# DTX1-1740P.net
KiCad netlist of a schematic drawn in Altium Designer
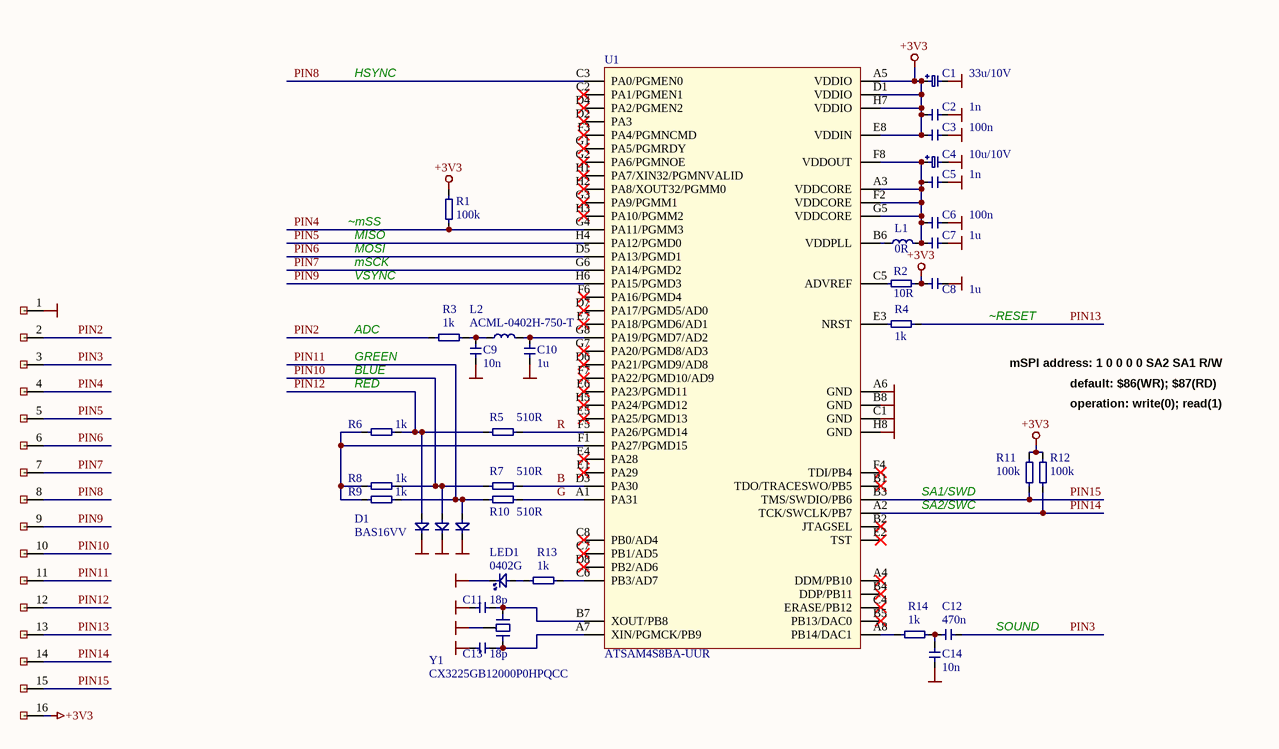
[diagram p0: DTX1-1740P.SchDoc]

(export (version "E")
  (design (tool "Eeschema 10.0.6"))
  (components
    (comp (ref "C1")
      (value "33u/10V")
      (footprint "Case A (3216)")
      (description "Polar capacitor")
      (libsource (lib "Discretes") (part "Capacitor+"))
    )
    (comp (ref "C2")
      (value "1n")
      (footprint "_0201")
      (description "Capacitor")
      (libsource (lib "Discretes") (part "Capacitor"))
    )
    (comp (ref "C3")
      (value "100n")
      (footprint "_0201")
      (description "Capacitor")
      (libsource (lib "Discretes") (part "Capacitor"))
    )
    (comp (ref "C4")
      (value "10u/10V")
      (footprint "_0805+")
      (description "Polar capacitor")
      (libsource (lib "Discretes") (part "Capacitor+"))
    )
    (comp (ref "C5")
      (value "1n")
      (footprint "_0201")
      (description "Capacitor")
      (libsource (lib "Discretes") (part "Capacitor"))
    )
    (comp (ref "C6")
      (value "100n")
      (footprint "_0201")
      (description "Capacitor")
      (libsource (lib "Discretes") (part "Capacitor"))
    )
    (comp (ref "C7")
      (value "1u")
      (footprint "_0201")
      (description "Capacitor")
      (libsource (lib "Discretes") (part "Capacitor"))
    )
    (comp (ref "C8")
      (value "1u")
      (footprint "_0201")
      (description "Capacitor")
      (libsource (lib "Discretes") (part "Capacitor"))
    )
    (comp (ref "C9")
      (value "10n")
      (footprint "_0201")
      (description "Capacitor")
      (libsource (lib "Discretes") (part "Capacitor"))
    )
    (comp (ref "C10")
      (value "1u")
      (footprint "_0201")
      (description "Capacitor")
      (libsource (lib "Discretes") (part "Capacitor"))
    )
    (comp (ref "C11")
      (value "18p")
      (footprint "_0201")
      (description "Capacitor")
      (libsource (lib "Discretes") (part "Capacitor"))
    )
    (comp (ref "C12")
      (value "470n")
      (footprint "_0201")
      (description "Capacitor")
      (libsource (lib "Discretes") (part "Capacitor"))
    )
    (comp (ref "C13")
      (value "18p")
      (footprint "_0201")
      (description "Capacitor")
      (libsource (lib "Discretes") (part "Capacitor"))
    )
    (comp (ref "C14")
      (value "10n")
      (footprint "_0201")
      (description "Capacitor")
      (libsource (lib "Discretes") (part "Capacitor"))
    )
    (comp (ref "D1")
      (value "BAS16VV")
      (footprint "SOT666-6")
      (description "Diode (triple)")
      (libsource (lib "Discretes") (part "Diode Triple"))
    )
    (comp (ref "L1")
      (value "0R")
      (footprint "_0402")
      (description "Inductor")
      (libsource (lib "Discretes") (part "Inductor"))
    )
    (comp (ref "L2")
      (value "ACML-0402H-750-T")
      (footprint "_0402")
      (description "Inductor")
      (libsource (lib "Discretes") (part "Inductor"))
    )
    (comp (ref "LED1")
      (value "0402G")
      (footprint "_0402+")
      (description "Light Emitting Diode")
      (libsource (lib "Discretes") (part "LED"))
    )
    (comp (ref "PIN1")
      (value "Pin/Pad")
      (footprint "Pad T/H 45/90")
      (description "Single pin/pad")
      (libsource (lib "") (part "Pin/Pad_5"))
    )
    (comp (ref "PIN2")
      (value "Pin/Pad")
      (footprint "Pad T/H 45/90")
      (description "Single pin/pad")
      (libsource (lib "") (part "Pin/Pad_1"))
    )
    (comp (ref "PIN3")
      (value "Pin/Pad")
      (footprint "Pad T/H 45/90")
      (description "Single pin/pad")
      (libsource (lib "") (part "Pin/Pad_2"))
    )
    (comp (ref "PIN4")
      (value "Pin/Pad")
      (footprint "Pad T/H 45/90")
      (description "Single pin/pad")
      (libsource (lib "Connectors") (part "Pin/Pad"))
    )
    (comp (ref "PIN5")
      (value "Pin/Pad")
      (footprint "Pad T/H 45/90")
      (description "Single pin/pad")
      (libsource (lib "") (part "Pin/Pad_14"))
    )
    (comp (ref "PIN6")
      (value "Pin/Pad")
      (footprint "Pad T/H 45/90")
      (description "Single pin/pad")
      (libsource (lib "") (part "Pin/Pad_7"))
    )
    (comp (ref "PIN7")
      (value "Pin/Pad")
      (footprint "Pad T/H 45/90")
      (description "Single pin/pad")
      (libsource (lib "") (part "Pin/Pad_6"))
    )
    (comp (ref "PIN8")
      (value "Pin/Pad")
      (footprint "Pad T/H 45/90")
      (description "Single pin/pad")
      (libsource (lib "") (part "Pin/Pad_11"))
    )
    (comp (ref "PIN9")
      (value "Pin/Pad")
      (footprint "Pad T/H 45/90")
      (description "Single pin/pad")
      (libsource (lib "") (part "Pin/Pad_9"))
    )
    (comp (ref "PIN10")
      (value "Pin/Pad")
      (footprint "Pad T/H 45/90")
      (description "Single pin/pad")
      (libsource (lib "") (part "Pin/Pad_15"))
    )
    (comp (ref "PIN11")
      (value "Pin/Pad")
      (footprint "Pad T/H 45/90")
      (description "Single pin/pad")
      (libsource (lib "") (part "Pin/Pad_12"))
    )
    (comp (ref "PIN12")
      (value "Pin/Pad")
      (footprint "Pad T/H 45/90")
      (description "Single pin/pad")
      (libsource (lib "") (part "Pin/Pad_10"))
    )
    (comp (ref "PIN13")
      (value "Pin/Pad")
      (footprint "Pad T/H 45/90")
      (description "Single pin/pad")
      (libsource (lib "") (part "Pin/Pad_4"))
    )
    (comp (ref "PIN14")
      (value "Pin/Pad")
      (footprint "Pad T/H 45/90")
      (description "Single pin/pad")
      (libsource (lib "") (part "Pin/Pad_8"))
    )
    (comp (ref "PIN15")
      (value "Pin/Pad")
      (footprint "Pad T/H 45/90")
      (description "Single pin/pad")
      (libsource (lib "") (part "Pin/Pad_13"))
    )
    (comp (ref "PIN16")
      (value "Pin/Pad")
      (footprint "Pad T/H 45/90")
      (description "Single pin/pad")
      (libsource (lib "") (part "Pin/Pad_3"))
    )
    (comp (ref "R1")
      (value "100k")
      (footprint "_0201")
      (description "Resistor")
      (libsource (lib "") (part "Resistor_1"))
    )
    (comp (ref "R2")
      (value "10R")
      (footprint "_0201")
      (description "Resistor")
      (libsource (lib "Discretes") (part "Resistor"))
    )
    (comp (ref "R3")
      (value "1k")
      (footprint "_0201")
      (description "Resistor")
      (libsource (lib "Discretes") (part "Resistor"))
    )
    (comp (ref "R4")
      (value "1k")
      (footprint "_0201")
      (description "Resistor")
      (libsource (lib "Discretes") (part "Resistor"))
    )
    (comp (ref "R5")
      (value "510R")
      (footprint "_0201")
      (description "Resistor")
      (libsource (lib "Discretes") (part "Resistor"))
    )
    (comp (ref "R6")
      (value "1k")
      (footprint "_0201")
      (description "Resistor")
      (libsource (lib "Discretes") (part "Resistor"))
    )
    (comp (ref "R7")
      (value "510R")
      (footprint "_0201")
      (description "Resistor")
      (libsource (lib "Discretes") (part "Resistor"))
    )
    (comp (ref "R8")
      (value "1k")
      (footprint "_0201")
      (description "Resistor")
      (libsource (lib "Discretes") (part "Resistor"))
    )
    (comp (ref "R9")
      (value "1k")
      (footprint "_0201")
      (description "Resistor")
      (libsource (lib "Discretes") (part "Resistor"))
    )
    (comp (ref "R10")
      (value "510R")
      (footprint "_0201")
      (description "Resistor")
      (libsource (lib "Discretes") (part "Resistor"))
    )
    (comp (ref "R11")
      (value "100k")
      (footprint "_0201")
      (description "Resistor")
      (libsource (lib "") (part "Resistor_1"))
    )
    (comp (ref "R12")
      (value "100k")
      (footprint "_0201")
      (description "Resistor")
      (libsource (lib "") (part "Resistor_1"))
    )
    (comp (ref "R13")
      (value "1k")
      (footprint "_0201")
      (description "Resistor")
      (libsource (lib "Discretes") (part "Resistor"))
    )
    (comp (ref "R14")
      (value "1k")
      (footprint "_0201")
      (description "Resistor")
      (libsource (lib "") (part "Resistor_2"))
    )
    (comp (ref "U1")
      (value "ATSAM4S8BA-UUR")
      (footprint "WLCSP64")
      (description "ARM Cortex M4-based Flash MCU")
      (fields (field (name "MANUFACTURER") "Atmel"))
      (libsource (lib "IC Microcontrollers and Processors") (part "AT91SAM4S16Bx WLCSP64"))
    )
    (comp (ref "Y1")
      (value "CX3225GB12000P0HPQCC")
      (footprint "Crystal 32x25 (4)")
      (description "Crystal Resonator")
      (libsource (lib "Discretes") (part "Crystal (ground)"))
    )
  )
  (nets
    (net (code "1") (name "+3V3") (class "Default")
      (node (ref "C1") (pin "1") (pintype "passive"))
      (node (ref "C2") (pin "1") (pintype "passive"))
      (node (ref "C3") (pin "1") (pintype "passive"))
      (node (ref "C8") (pin "1") (pintype "passive"))
      (node (ref "PIN16") (pin "16") (pintype "passive"))
      (node (ref "R1") (pin "2") (pintype "passive"))
      (node (ref "R11") (pin "2") (pintype "passive"))
      (node (ref "R12") (pin "2") (pintype "passive"))
      (node (ref "R2") (pin "2") (pintype "passive"))
      (node (ref "U1") (pin "A5") (pinfunction "VDDIO_A5") (pintype "passive"))
      (node (ref "U1") (pin "D1") (pinfunction "VDDIO_D1") (pintype "passive"))
      (node (ref "U1") (pin "E8") (pinfunction "VDDIN_E8") (pintype "passive"))
      (node (ref "U1") (pin "H7") (pinfunction "VDDIO_H7") (pintype "passive"))
    )
    (net (code "2") (name "/B") (class "Default")
      (node (ref "R7") (pin "2") (pintype "passive"))
      (node (ref "U1") (pin "D3") (pinfunction "PA30_D3") (pintype "passive"))
    )
    (net (code "3") (name "/G") (class "Default")
      (node (ref "R10") (pin "2") (pintype "passive"))
      (node (ref "U1") (pin "A1") (pinfunction "PA31_A1") (pintype "passive"))
    )
    (net (code "4") (name "/PIN2") (class "Default")
      (node (ref "PIN2") (pin "2") (pintype "passive"))
      (node (ref "R3") (pin "1") (pintype "passive"))
    )
    (net (code "5") (name "/PIN3") (class "Default")
      (node (ref "C12") (pin "2") (pintype "passive"))
      (node (ref "PIN3") (pin "3") (pintype "passive"))
    )
    (net (code "6") (name "/PIN4") (class "Default")
      (node (ref "PIN4") (pin "4") (pintype "passive"))
      (node (ref "R1") (pin "1") (pintype "passive"))
      (node (ref "U1") (pin "G4") (pinfunction "PA11/PGMM3_G4") (pintype "passive"))
    )
    (net (code "7") (name "/PIN5") (class "Default")
      (node (ref "PIN5") (pin "5") (pintype "passive"))
      (node (ref "U1") (pin "H4") (pinfunction "PA12/PGMD0_H4") (pintype "passive"))
    )
    (net (code "8") (name "/PIN6") (class "Default")
      (node (ref "PIN6") (pin "6") (pintype "passive"))
      (node (ref "U1") (pin "D5") (pinfunction "PA13/PGMD1_D5") (pintype "passive"))
    )
    (net (code "9") (name "/PIN7") (class "Default")
      (node (ref "PIN7") (pin "7") (pintype "passive"))
      (node (ref "U1") (pin "G6") (pinfunction "PA14/PGMD2_G6") (pintype "passive"))
    )
    (net (code "10") (name "/PIN8") (class "Default")
      (node (ref "PIN8") (pin "8") (pintype "passive"))
      (node (ref "U1") (pin "C3") (pinfunction "PA0/PGMEN0_C3") (pintype "passive"))
    )
    (net (code "11") (name "/PIN9") (class "Default")
      (node (ref "PIN9") (pin "9") (pintype "passive"))
      (node (ref "U1") (pin "H6") (pinfunction "PA15/PGMD3_H6") (pintype "passive"))
    )
    (net (code "12") (name "/PIN10") (class "Default")
      (node (ref "D1") (pin "2") (pintype "passive"))
      (node (ref "PIN10") (pin "10") (pintype "passive"))
      (node (ref "R7") (pin "1") (pintype "passive"))
      (node (ref "R8") (pin "2") (pintype "passive"))
    )
    (net (code "13") (name "/PIN11") (class "Default")
      (node (ref "D1") (pin "3") (pintype "passive"))
      (node (ref "PIN11") (pin "11") (pintype "passive"))
      (node (ref "R10") (pin "1") (pintype "passive"))
      (node (ref "R9") (pin "2") (pintype "passive"))
    )
    (net (code "14") (name "/PIN12") (class "Default")
      (node (ref "D1") (pin "1") (pintype "passive"))
      (node (ref "PIN12") (pin "12") (pintype "passive"))
      (node (ref "R5") (pin "1") (pintype "passive"))
      (node (ref "R6") (pin "2") (pintype "passive"))
    )
    (net (code "15") (name "/PIN13") (class "Default")
      (node (ref "PIN13") (pin "13") (pintype "passive"))
      (node (ref "R4") (pin "2") (pintype "passive"))
    )
    (net (code "16") (name "/PIN14") (class "Default")
      (node (ref "PIN14") (pin "14") (pintype "passive"))
      (node (ref "R12") (pin "1") (pintype "passive"))
      (node (ref "U1") (pin "A2") (pinfunction "TCK/SWCLK/PB7_A2") (pintype "passive"))
    )
    (net (code "17") (name "/PIN15") (class "Default")
      (node (ref "PIN15") (pin "15") (pintype "passive"))
      (node (ref "R11") (pin "1") (pintype "passive"))
      (node (ref "U1") (pin "B3") (pinfunction "TMS/SWDIO/PB6_B3") (pintype "passive"))
    )
    (net (code "18") (name "/R") (class "Default")
      (node (ref "R5") (pin "2") (pintype "passive"))
      (node (ref "U1") (pin "F5") (pinfunction "PA26/PGMD14_F5") (pintype "passive"))
    )
    (net (code "19") (name "GND") (class "Default")
      (node (ref "C1") (pin "2") (pintype "passive"))
      (node (ref "C10") (pin "1") (pintype "passive"))
      (node (ref "C11") (pin "1") (pintype "passive"))
      (node (ref "C13") (pin "1") (pintype "passive"))
      (node (ref "C14") (pin "1") (pintype "passive"))
      (node (ref "C2") (pin "2") (pintype "passive"))
      (node (ref "C3") (pin "2") (pintype "passive"))
      (node (ref "C4") (pin "2") (pintype "passive"))
      (node (ref "C5") (pin "2") (pintype "passive"))
      (node (ref "C6") (pin "2") (pintype "passive"))
      (node (ref "C7") (pin "2") (pintype "passive"))
      (node (ref "C8") (pin "2") (pintype "passive"))
      (node (ref "C9") (pin "1") (pintype "passive"))
      (node (ref "D1") (pin "4") (pintype "passive"))
      (node (ref "D1") (pin "5") (pintype "passive"))
      (node (ref "D1") (pin "6") (pintype "passive"))
      (node (ref "LED1") (pin "1") (pintype "passive"))
      (node (ref "PIN1") (pin "1") (pintype "passive"))
      (node (ref "U1") (pin "A6") (pinfunction "GND_A6") (pintype "passive"))
      (node (ref "U1") (pin "B8") (pinfunction "GND_B8") (pintype "passive"))
      (node (ref "U1") (pin "C1") (pinfunction "GND_C1") (pintype "passive"))
      (node (ref "U1") (pin "H8") (pinfunction "GND_H8") (pintype "passive"))
      (node (ref "Y1") (pin "3") (pinfunction "GND_3") (pintype "passive"))
    )
    (net (code "20") (name "Net-(C9-Pad2)") (class "Default")
      (node (ref "C9") (pin "2") (pintype "passive"))
      (node (ref "L2") (pin "1") (pintype "passive"))
      (node (ref "R3") (pin "2") (pintype "passive"))
    )
    (net (code "21") (name "Net-(C12-Pad1)") (class "Default")
      (node (ref "C12") (pin "1") (pintype "passive"))
      (node (ref "C14") (pin "2") (pintype "passive"))
      (node (ref "R14") (pin "1") (pintype "passive"))
    )
    (net (code "22") (name "Net-(LED1-Pad2)") (class "Default")
      (node (ref "LED1") (pin "2") (pintype "passive"))
      (node (ref "R13") (pin "1") (pintype "passive"))
    )
    (net (code "23") (name "Net-(U1-ADVREF)") (class "Default")
      (node (ref "R2") (pin "1") (pintype "passive"))
      (node (ref "U1") (pin "C5") (pinfunction "ADVREF_C5") (pintype "passive"))
    )
    (net (code "24") (name "Net-(U1-NRST)") (class "Default")
      (node (ref "R4") (pin "1") (pintype "passive"))
      (node (ref "U1") (pin "E3") (pinfunction "NRST_E3") (pintype "passive"))
    )
    (net (code "25") (name "Net-(U1-PA19{slash}PGMD7{slash}AD2)") (class "Default")
      (node (ref "C10") (pin "2") (pintype "passive"))
      (node (ref "L2") (pin "2") (pintype "passive"))
      (node (ref "U1") (pin "G8") (pinfunction "PA19/PGMD7/AD2_G8") (pintype "passive"))
    )
    (net (code "26") (name "Net-(U1-PA27{slash}PGMD15)") (class "Default")
      (node (ref "R6") (pin "1") (pintype "passive"))
      (node (ref "R8") (pin "1") (pintype "passive"))
      (node (ref "R9") (pin "1") (pintype "passive"))
      (node (ref "U1") (pin "F1") (pinfunction "PA27/PGMD15_F1") (pintype "passive"))
    )
    (net (code "27") (name "Net-(U1-PB3{slash}AD7)") (class "Default")
      (node (ref "R13") (pin "2") (pintype "passive"))
      (node (ref "U1") (pin "C6") (pinfunction "PB3/AD7_C6") (pintype "passive"))
    )
    (net (code "28") (name "Net-(U1-PB14{slash}DAC1)") (class "Default")
      (node (ref "R14") (pin "2") (pintype "passive"))
      (node (ref "U1") (pin "A8") (pinfunction "PB14/DAC1_A8") (pintype "passive"))
    )
    (net (code "29") (name "Net-(U1-VDDOUT)") (class "Default")
      (node (ref "C4") (pin "1") (pintype "passive"))
      (node (ref "C5") (pin "1") (pintype "passive"))
      (node (ref "C6") (pin "1") (pintype "passive"))
      (node (ref "C7") (pin "1") (pintype "passive"))
      (node (ref "L1") (pin "2") (pintype "passive"))
      (node (ref "U1") (pin "A3") (pinfunction "VDDCORE_A3") (pintype "passive"))
      (node (ref "U1") (pin "F2") (pinfunction "VDDCORE_F2") (pintype "passive"))
      (node (ref "U1") (pin "F8") (pinfunction "VDDOUT_F8") (pintype "passive"))
      (node (ref "U1") (pin "G5") (pinfunction "VDDCORE_G5") (pintype "passive"))
    )
    (net (code "30") (name "Net-(U1-VDDPLL)") (class "Default")
      (node (ref "L1") (pin "1") (pintype "passive"))
      (node (ref "U1") (pin "B6") (pinfunction "VDDPLL_B6") (pintype "passive"))
    )
    (net (code "31") (name "Net-(U1-XIN{slash}PGMCK{slash}PB9)") (class "Default")
      (node (ref "C13") (pin "2") (pintype "passive"))
      (node (ref "U1") (pin "A7") (pinfunction "XIN/PGMCK/PB9_A7") (pintype "passive"))
      (node (ref "Y1") (pin "1") (pintype "passive"))
    )
    (net (code "32") (name "Net-(U1-XOUT{slash}PB8)") (class "Default")
      (node (ref "C11") (pin "2") (pintype "passive"))
      (node (ref "U1") (pin "B7") (pinfunction "XOUT/PB8_B7") (pintype "passive"))
      (node (ref "Y1") (pin "2") (pintype "passive"))
    )
    (net (code "33") (name "unconnected-(U1-DDM{slash}PB10-PadA4)") (class "Default")
      (node (ref "U1") (pin "A4") (pinfunction "DDM/PB10_A4") (pintype "passive+no_connect"))
    )
    (net (code "34") (name "unconnected-(U1-DDP{slash}PB11-PadB4)") (class "Default")
      (node (ref "U1") (pin "B4") (pinfunction "DDP/PB11_B4") (pintype "passive+no_connect"))
    )
    (net (code "35") (name "unconnected-(U1-ERASE{slash}PB12-PadC4)") (class "Default")
      (node (ref "U1") (pin "C4") (pinfunction "ERASE/PB12_C4") (pintype "passive+no_connect"))
    )
    (net (code "36") (name "unconnected-(U1-JTAGSEL-PadB2)") (class "Default")
      (node (ref "U1") (pin "B2") (pinfunction "JTAGSEL_B2") (pintype "passive+no_connect"))
    )
    (net (code "37") (name "unconnected-(U1-PA1{slash}PGMEN1-PadC2)") (class "Default")
      (node (ref "U1") (pin "C2") (pinfunction "PA1/PGMEN1_C2") (pintype "passive+no_connect"))
    )
    (net (code "38") (name "unconnected-(U1-PA2{slash}PGMEN2-PadD4)") (class "Default")
      (node (ref "U1") (pin "D4") (pinfunction "PA2/PGMEN2_D4") (pintype "passive+no_connect"))
    )
    (net (code "39") (name "unconnected-(U1-PA3-PadD2)") (class "Default")
      (node (ref "U1") (pin "D2") (pinfunction "PA3_D2") (pintype "passive+no_connect"))
    )
    (net (code "40") (name "unconnected-(U1-PA4{slash}PGMNCMD-PadF3)") (class "Default")
      (node (ref "U1") (pin "F3") (pinfunction "PA4/PGMNCMD_F3") (pintype "passive+no_connect"))
    )
    (net (code "41") (name "unconnected-(U1-PA5{slash}PGMRDY-PadG1)") (class "Default")
      (node (ref "U1") (pin "G1") (pinfunction "PA5/PGMRDY_G1") (pintype "passive+no_connect"))
    )
    (net (code "42") (name "unconnected-(U1-PA6{slash}PGMNOE-PadG2)") (class "Default")
      (node (ref "U1") (pin "G2") (pinfunction "PA6/PGMNOE_G2") (pintype "passive+no_connect"))
    )
    (net (code "43") (name "unconnected-(U1-PA7{slash}XIN32{slash}PGMNVALID-PadH1)") (class "Default")
      (node (ref "U1") (pin "H1") (pinfunction "PA7/XIN32/PGMNVALID_H1") (pintype "passive+no_connect"))
    )
    (net (code "44") (name "unconnected-(U1-PA8{slash}XOUT32{slash}PGMM0-PadH2)") (class "Default")
      (node (ref "U1") (pin "H2") (pinfunction "PA8/XOUT32/PGMM0_H2") (pintype "passive+no_connect"))
    )
    (net (code "45") (name "unconnected-(U1-PA9{slash}PGMM1-PadG3)") (class "Default")
      (node (ref "U1") (pin "G3") (pinfunction "PA9/PGMM1_G3") (pintype "passive+no_connect"))
    )
    (net (code "46") (name "unconnected-(U1-PA10{slash}PGMM2-PadH3)") (class "Default")
      (node (ref "U1") (pin "H3") (pinfunction "PA10/PGMM2_H3") (pintype "passive+no_connect"))
    )
    (net (code "47") (name "unconnected-(U1-PA16{slash}PGMD4-PadF6)") (class "Default")
      (node (ref "U1") (pin "F6") (pinfunction "PA16/PGMD4_F6") (pintype "passive+no_connect"))
    )
    (net (code "48") (name "unconnected-(U1-PA17{slash}PGMD5{slash}AD0-PadD7)") (class "Default")
      (node (ref "U1") (pin "D7") (pinfunction "PA17/PGMD5/AD0_D7") (pintype "passive+no_connect"))
    )
    (net (code "49") (name "unconnected-(U1-PA18{slash}PGMD6{slash}AD1-PadE7)") (class "Default")
      (node (ref "U1") (pin "E7") (pinfunction "PA18/PGMD6/AD1_E7") (pintype "passive+no_connect"))
    )
    (net (code "50") (name "unconnected-(U1-PA20{slash}PGMD8{slash}AD3-PadG7)") (class "Default")
      (node (ref "U1") (pin "G7") (pinfunction "PA20/PGMD8/AD3_G7") (pintype "passive+no_connect"))
    )
    (net (code "51") (name "unconnected-(U1-PA21{slash}PGMD9{slash}AD8-PadD6)") (class "Default")
      (node (ref "U1") (pin "D6") (pinfunction "PA21/PGMD9/AD8_D6") (pintype "passive+no_connect"))
    )
    (net (code "52") (name "unconnected-(U1-PA22{slash}PGMD10{slash}AD9-PadF7)") (class "Default")
      (node (ref "U1") (pin "F7") (pinfunction "PA22/PGMD10/AD9_F7") (pintype "passive+no_connect"))
    )
    (net (code "53") (name "unconnected-(U1-PA23{slash}PGMD11-PadE6)") (class "Default")
      (node (ref "U1") (pin "E6") (pinfunction "PA23/PGMD11_E6") (pintype "passive+no_connect"))
    )
    (net (code "54") (name "unconnected-(U1-PA24{slash}PGMD12-PadH5)") (class "Default")
      (node (ref "U1") (pin "H5") (pinfunction "PA24/PGMD12_H5") (pintype "passive+no_connect"))
    )
    (net (code "55") (name "unconnected-(U1-PA25{slash}PGMD13-PadE5)") (class "Default")
      (node (ref "U1") (pin "E5") (pinfunction "PA25/PGMD13_E5") (pintype "passive+no_connect"))
    )
    (net (code "56") (name "unconnected-(U1-PA28-PadE4)") (class "Default")
      (node (ref "U1") (pin "E4") (pinfunction "PA28_E4") (pintype "passive+no_connect"))
    )
    (net (code "57") (name "unconnected-(U1-PA29-PadE1)") (class "Default")
      (node (ref "U1") (pin "E1") (pinfunction "PA29_E1") (pintype "passive+no_connect"))
    )
    (net (code "58") (name "unconnected-(U1-PB0{slash}AD4-PadC8)") (class "Default")
      (node (ref "U1") (pin "C8") (pinfunction "PB0/AD4_C8") (pintype "passive+no_connect"))
    )
    (net (code "59") (name "unconnected-(U1-PB1{slash}AD5-PadC7)") (class "Default")
      (node (ref "U1") (pin "C7") (pinfunction "PB1/AD5_C7") (pintype "passive+no_connect"))
    )
    (net (code "60") (name "unconnected-(U1-PB2{slash}AD6-PadD8)") (class "Default")
      (node (ref "U1") (pin "D8") (pinfunction "PB2/AD6_D8") (pintype "passive+no_connect"))
    )
    (net (code "61") (name "unconnected-(U1-PB13{slash}DAC0-PadB5)") (class "Default")
      (node (ref "U1") (pin "B5") (pinfunction "PB13/DAC0_B5") (pintype "passive+no_connect"))
    )
    (net (code "62") (name "unconnected-(U1-TDI{slash}PB4-PadF4)") (class "Default")
      (node (ref "U1") (pin "F4") (pinfunction "TDI/PB4_F4") (pintype "passive+no_connect"))
    )
    (net (code "63") (name "unconnected-(U1-TDO{slash}TRACESWO{slash}PB5-PadB1)") (class "Default")
      (node (ref "U1") (pin "B1") (pinfunction "TDO/TRACESWO/PB5_B1") (pintype "passive+no_connect"))
    )
    (net (code "64") (name "unconnected-(U1-TST-PadE2)") (class "Default")
      (node (ref "U1") (pin "E2") (pinfunction "TST_E2") (pintype "passive+no_connect"))
    )
  )
)
